# circuit.net
KiCad netlist of a schematic drawn in EAGLE
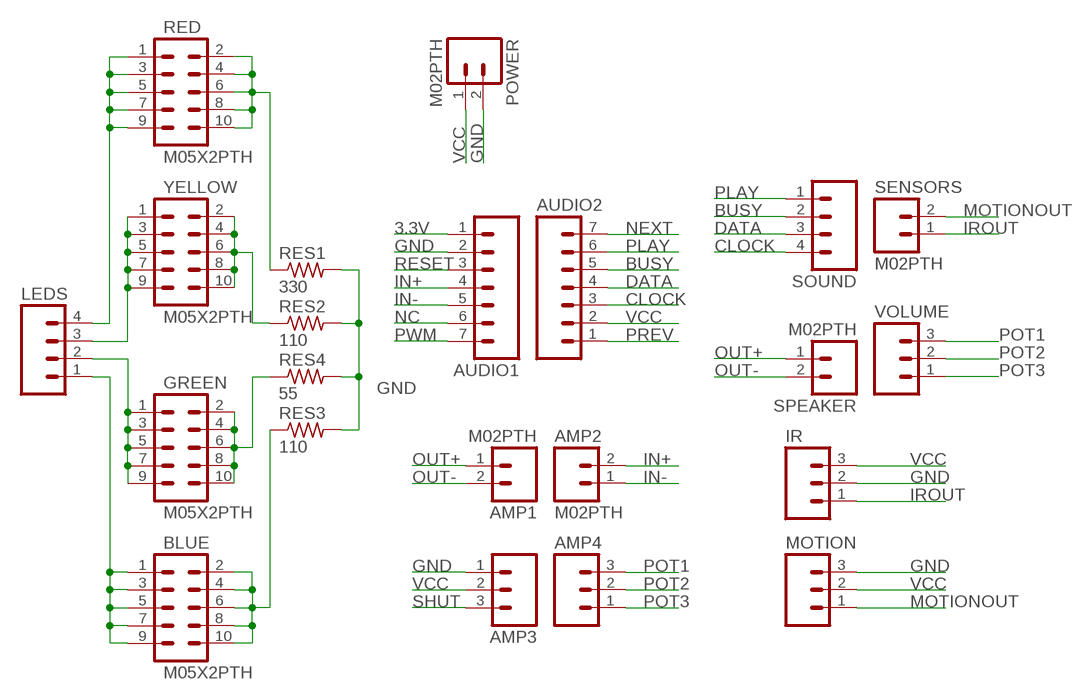
[diagram p0: schematic, sheet 1]

(export (version "E")
  (design (tool "Eeschema 10.0.6"))
  (components
    (comp (ref "AMP1")
      (value "M02PTH")
      (footprint "eagle-import:1X02")
      (libsource (lib "eagle-import") (part "M02PTH"))
    )
    (comp (ref "AMP2")
      (value "M02PTH")
      (footprint "eagle-import:1X02")
      (libsource (lib "eagle-import") (part "M02PTH"))
    )
    (comp (ref "AMP3")
      (value "M03PTH")
      (footprint "eagle-import:1X03")
      (libsource (lib "eagle-import") (part "M03PTH"))
    )
    (comp (ref "AMP4")
      (value "M03PTH")
      (footprint "eagle-import:1X03")
      (libsource (lib "eagle-import") (part "M03PTH"))
    )
    (comp (ref "AUDIO1")
      (value "M07")
      (footprint "eagle-import:1X07")
      (libsource (lib "eagle-import") (part "M07"))
    )
    (comp (ref "AUDIO2")
      (value "M07")
      (footprint "eagle-import:1X07")
      (libsource (lib "eagle-import") (part "M07"))
    )
    (comp (ref "BLUE")
      (value "M05X2PTH")
      (footprint "eagle-import:AVR_ICSP")
      (libsource (lib "eagle-import") (part "M05X2PTH"))
    )
    (comp (ref "GREEN")
      (value "M05X2PTH")
      (footprint "eagle-import:AVR_ICSP")
      (libsource (lib "eagle-import") (part "M05X2PTH"))
    )
    (comp (ref "IR")
      (value "M03PTH")
      (footprint "eagle-import:1X03")
      (libsource (lib "eagle-import") (part "M03PTH"))
    )
    (comp (ref "LEDS")
      (value "M04PTH")
      (footprint "eagle-import:1X04")
      (libsource (lib "eagle-import") (part "M04PTH"))
    )
    (comp (ref "MOTION")
      (value "M03PTH")
      (footprint "eagle-import:1X03")
      (libsource (lib "eagle-import") (part "M03PTH"))
    )
    (comp (ref "POWER")
      (value "M02PTH")
      (footprint "eagle-import:1X02")
      (libsource (lib "eagle-import") (part "M02PTH"))
    )
    (comp (ref "RED")
      (value "M05X2PTH")
      (footprint "eagle-import:AVR_ICSP")
      (libsource (lib "eagle-import") (part "M05X2PTH"))
    )
    (comp (ref "RES1")
      (value "330")
      (footprint "eagle-import:0204V")
      (libsource (lib "eagle-import") (part "R-US_0204/2V"))
    )
    (comp (ref "RES2")
      (value "110")
      (footprint "eagle-import:0204V")
      (libsource (lib "eagle-import") (part "R-US_0204/2V"))
    )
    (comp (ref "RES3")
      (value "110")
      (footprint "eagle-import:0204V")
      (libsource (lib "eagle-import") (part "R-US_0204/2V"))
    )
    (comp (ref "RES4")
      (value "55")
      (footprint "eagle-import:0204V")
      (libsource (lib "eagle-import") (part "R-US_0204/2V"))
    )
    (comp (ref "SENSORS")
      (value "M02PTH")
      (footprint "eagle-import:1X02")
      (libsource (lib "eagle-import") (part "M02PTH"))
    )
    (comp (ref "SOUND")
      (value "M04PTH")
      (footprint "eagle-import:1X04")
      (libsource (lib "eagle-import") (part "M04PTH"))
    )
    (comp (ref "SPEAKER")
      (value "M02PTH")
      (footprint "eagle-import:1X02")
      (libsource (lib "eagle-import") (part "M02PTH"))
    )
    (comp (ref "VOLUME")
      (value "M03PTH")
      (footprint "eagle-import:1X03")
      (libsource (lib "eagle-import") (part "M03PTH"))
    )
    (comp (ref "YELLOW")
      (value "M05X2PTH")
      (footprint "eagle-import:AVR_ICSP")
      (libsource (lib "eagle-import") (part "M05X2PTH"))
    )
  )
  (nets
    (net (code "1") (name "/3.3V") (class "Default")
      (node (ref "AUDIO1") (pin "1") (pinfunction "1_1") (pintype "passive"))
    )
    (net (code "2") (name "/BUSY") (class "Default")
      (node (ref "AUDIO2") (pin "5") (pinfunction "5_5") (pintype "passive"))
      (node (ref "SOUND") (pin "2") (pinfunction "2_2") (pintype "passive"))
    )
    (net (code "3") (name "/CLOCK") (class "Default")
      (node (ref "AUDIO2") (pin "3") (pinfunction "3_3") (pintype "passive"))
      (node (ref "SOUND") (pin "4") (pinfunction "4_4") (pintype "passive"))
    )
    (net (code "4") (name "/DATA") (class "Default")
      (node (ref "AUDIO2") (pin "4") (pinfunction "4_4") (pintype "passive"))
      (node (ref "SOUND") (pin "3") (pinfunction "3_3") (pintype "passive"))
    )
    (net (code "5") (name "/GND") (class "Default")
      (node (ref "AMP3") (pin "1") (pinfunction "1_1") (pintype "passive"))
      (node (ref "AUDIO1") (pin "2") (pinfunction "2_2") (pintype "passive"))
      (node (ref "IR") (pin "2") (pinfunction "2_2") (pintype "passive"))
      (node (ref "MOTION") (pin "3") (pinfunction "3_3") (pintype "passive"))
      (node (ref "POWER") (pin "2") (pinfunction "2_2") (pintype "passive"))
      (node (ref "RES1") (pin "2") (pinfunction "2_2") (pintype "passive"))
      (node (ref "RES2") (pin "2") (pinfunction "2_2") (pintype "passive"))
      (node (ref "RES3") (pin "2") (pinfunction "2_2") (pintype "passive"))
      (node (ref "RES4") (pin "2") (pinfunction "2_2") (pintype "passive"))
    )
    (net (code "6") (name "/IN+") (class "Default")
      (node (ref "AMP2") (pin "2") (pinfunction "2_2") (pintype "passive"))
      (node (ref "AUDIO1") (pin "4") (pinfunction "4_4") (pintype "passive"))
    )
    (net (code "7") (name "/IN-") (class "Default")
      (node (ref "AMP2") (pin "1") (pinfunction "1_1") (pintype "passive"))
      (node (ref "AUDIO1") (pin "5") (pinfunction "5_5") (pintype "passive"))
    )
    (net (code "8") (name "/IROUT") (class "Default")
      (node (ref "IR") (pin "1") (pinfunction "1_1") (pintype "passive"))
      (node (ref "SENSORS") (pin "1") (pinfunction "1_1") (pintype "passive"))
    )
    (net (code "9") (name "/MOTIONOUT") (class "Default")
      (node (ref "MOTION") (pin "1") (pinfunction "1_1") (pintype "passive"))
      (node (ref "SENSORS") (pin "2") (pinfunction "2_2") (pintype "passive"))
    )
    (net (code "10") (name "/NC") (class "Default")
      (node (ref "AUDIO1") (pin "6") (pinfunction "6_6") (pintype "passive"))
    )
    (net (code "11") (name "/NEXT") (class "Default")
      (node (ref "AUDIO2") (pin "7") (pinfunction "7_7") (pintype "passive"))
    )
    (net (code "12") (name "/OUT+") (class "Default")
      (node (ref "AMP1") (pin "1") (pinfunction "1_1") (pintype "passive"))
      (node (ref "SPEAKER") (pin "1") (pinfunction "1_1") (pintype "passive"))
    )
    (net (code "13") (name "/OUT-") (class "Default")
      (node (ref "AMP1") (pin "2") (pinfunction "2_2") (pintype "passive"))
      (node (ref "SPEAKER") (pin "2") (pinfunction "2_2") (pintype "passive"))
    )
    (net (code "14") (name "/PLAY") (class "Default")
      (node (ref "AUDIO2") (pin "6") (pinfunction "6_6") (pintype "passive"))
      (node (ref "SOUND") (pin "1") (pinfunction "1_1") (pintype "passive"))
    )
    (net (code "15") (name "/POT1") (class "Default")
      (node (ref "AMP4") (pin "3") (pinfunction "3_3") (pintype "passive"))
      (node (ref "VOLUME") (pin "3") (pinfunction "3_3") (pintype "passive"))
    )
    (net (code "16") (name "/POT2") (class "Default")
      (node (ref "AMP4") (pin "2") (pinfunction "2_2") (pintype "passive"))
      (node (ref "VOLUME") (pin "2") (pinfunction "2_2") (pintype "passive"))
    )
    (net (code "17") (name "/POT3") (class "Default")
      (node (ref "AMP4") (pin "1") (pinfunction "1_1") (pintype "passive"))
      (node (ref "VOLUME") (pin "1") (pinfunction "1_1") (pintype "passive"))
    )
    (net (code "18") (name "/PREV") (class "Default")
      (node (ref "AUDIO2") (pin "1") (pinfunction "1_1") (pintype "passive"))
    )
    (net (code "19") (name "/PWM") (class "Default")
      (node (ref "AUDIO1") (pin "7") (pinfunction "7_7") (pintype "passive"))
    )
    (net (code "20") (name "/RESET") (class "Default")
      (node (ref "AUDIO1") (pin "3") (pinfunction "3_3") (pintype "passive"))
    )
    (net (code "21") (name "/SHUT") (class "Default")
      (node (ref "AMP3") (pin "3") (pinfunction "3_3") (pintype "passive"))
    )
    (net (code "22") (name "/VCC") (class "Default")
      (node (ref "AMP3") (pin "2") (pinfunction "2_2") (pintype "passive"))
      (node (ref "AUDIO2") (pin "2") (pinfunction "2_2") (pintype "passive"))
      (node (ref "IR") (pin "3") (pinfunction "3_3") (pintype "passive"))
      (node (ref "MOTION") (pin "2") (pinfunction "2_2") (pintype "passive"))
      (node (ref "POWER") (pin "1") (pinfunction "1_1") (pintype "passive"))
    )
    (net (code "23") (name "Net-(BLUE-Pad1)") (class "Default")
      (node (ref "BLUE") (pin "1") (pinfunction "1_1") (pintype "passive"))
      (node (ref "BLUE") (pin "3") (pinfunction "3_3") (pintype "passive"))
      (node (ref "BLUE") (pin "5") (pinfunction "5_5") (pintype "passive"))
      (node (ref "BLUE") (pin "7") (pinfunction "7_7") (pintype "passive"))
      (node (ref "BLUE") (pin "9") (pinfunction "9_9") (pintype "passive"))
      (node (ref "LEDS") (pin "1") (pinfunction "1_1") (pintype "passive"))
    )
    (net (code "24") (name "Net-(BLUE-Pad10)") (class "Default")
      (node (ref "BLUE") (pin "10") (pinfunction "10_10") (pintype "passive"))
      (node (ref "BLUE") (pin "2") (pinfunction "2_2") (pintype "passive"))
      (node (ref "BLUE") (pin "4") (pinfunction "4_4") (pintype "passive"))
      (node (ref "BLUE") (pin "6") (pinfunction "6_6") (pintype "passive"))
      (node (ref "BLUE") (pin "8") (pinfunction "8_8") (pintype "passive"))
      (node (ref "RES3") (pin "1") (pinfunction "1_1") (pintype "passive"))
    )
    (net (code "25") (name "Net-(GREEN-Pad1)") (class "Default")
      (node (ref "GREEN") (pin "1") (pinfunction "1_1") (pintype "passive"))
      (node (ref "GREEN") (pin "3") (pinfunction "3_3") (pintype "passive"))
      (node (ref "GREEN") (pin "5") (pinfunction "5_5") (pintype "passive"))
      (node (ref "GREEN") (pin "7") (pinfunction "7_7") (pintype "passive"))
      (node (ref "GREEN") (pin "9") (pinfunction "9_9") (pintype "passive"))
      (node (ref "LEDS") (pin "2") (pinfunction "2_2") (pintype "passive"))
    )
    (net (code "26") (name "Net-(GREEN-Pad10)") (class "Default")
      (node (ref "GREEN") (pin "10") (pinfunction "10_10") (pintype "passive"))
      (node (ref "GREEN") (pin "2") (pinfunction "2_2") (pintype "passive"))
      (node (ref "GREEN") (pin "4") (pinfunction "4_4") (pintype "passive"))
      (node (ref "GREEN") (pin "6") (pinfunction "6_6") (pintype "passive"))
      (node (ref "GREEN") (pin "8") (pinfunction "8_8") (pintype "passive"))
      (node (ref "RES4") (pin "1") (pinfunction "1_1") (pintype "passive"))
    )
    (net (code "27") (name "Net-(LEDS-Pad3)") (class "Default")
      (node (ref "LEDS") (pin "3") (pinfunction "3_3") (pintype "passive"))
      (node (ref "YELLOW") (pin "1") (pinfunction "1_1") (pintype "passive"))
      (node (ref "YELLOW") (pin "3") (pinfunction "3_3") (pintype "passive"))
      (node (ref "YELLOW") (pin "5") (pinfunction "5_5") (pintype "passive"))
      (node (ref "YELLOW") (pin "7") (pinfunction "7_7") (pintype "passive"))
      (node (ref "YELLOW") (pin "9") (pinfunction "9_9") (pintype "passive"))
    )
    (net (code "28") (name "Net-(LEDS-Pad4)") (class "Default")
      (node (ref "LEDS") (pin "4") (pinfunction "4_4") (pintype "passive"))
      (node (ref "RED") (pin "1") (pinfunction "1_1") (pintype "passive"))
      (node (ref "RED") (pin "3") (pinfunction "3_3") (pintype "passive"))
      (node (ref "RED") (pin "5") (pinfunction "5_5") (pintype "passive"))
      (node (ref "RED") (pin "7") (pinfunction "7_7") (pintype "passive"))
      (node (ref "RED") (pin "9") (pinfunction "9_9") (pintype "passive"))
    )
    (net (code "29") (name "Net-(RED-Pad10)") (class "Default")
      (node (ref "RED") (pin "10") (pinfunction "10_10") (pintype "passive"))
      (node (ref "RED") (pin "2") (pinfunction "2_2") (pintype "passive"))
      (node (ref "RED") (pin "4") (pinfunction "4_4") (pintype "passive"))
      (node (ref "RED") (pin "6") (pinfunction "6_6") (pintype "passive"))
      (node (ref "RED") (pin "8") (pinfunction "8_8") (pintype "passive"))
      (node (ref "RES1") (pin "1") (pinfunction "1_1") (pintype "passive"))
    )
    (net (code "30") (name "Net-(RES2-Pad1)") (class "Default")
      (node (ref "RES2") (pin "1") (pinfunction "1_1") (pintype "passive"))
      (node (ref "YELLOW") (pin "10") (pinfunction "10_10") (pintype "passive"))
      (node (ref "YELLOW") (pin "2") (pinfunction "2_2") (pintype "passive"))
      (node (ref "YELLOW") (pin "4") (pinfunction "4_4") (pintype "passive"))
      (node (ref "YELLOW") (pin "6") (pinfunction "6_6") (pintype "passive"))
      (node (ref "YELLOW") (pin "8") (pinfunction "8_8") (pintype "passive"))
    )
  )
)
